# 12V_FROM_BATTERY.net
KiCad netlist of a schematic drawn in Altium Designer
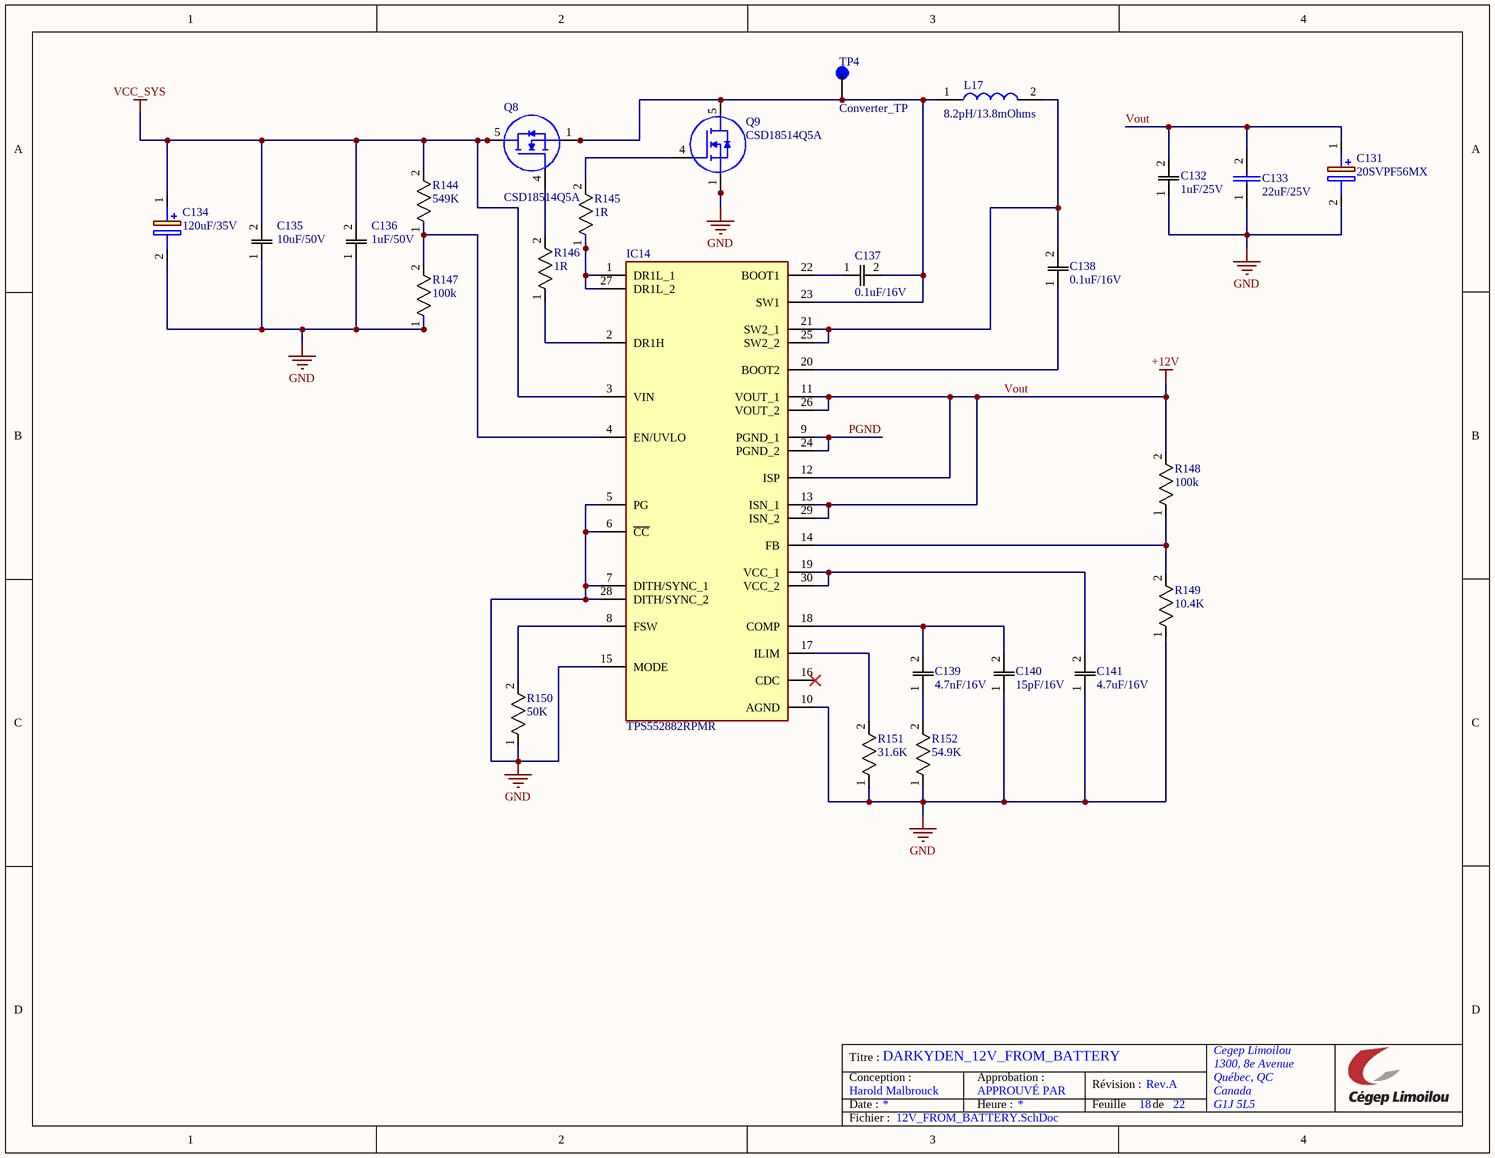
[diagram p0: 12V_FROM_BATTERY.SchDoc]

(export (version "E")
  (design (tool "Eeschema 10.0.6"))
  (components
    (comp (ref "C131")
      (value "20SVPF56MX")
      (footprint "SamacSys:16SVF82M")
      (description "56uF 20VDC 20%( Cap Aluminum Polymer SMD 0.03 Ohm 2800mA 5000h 105C T/R")
      (fields (field (name "MOUSER PART NUMBER") "667-20SVPF56MX") (field (name "MANUFACTURER") "Panasonic"))
      (libsource (lib "SamacSys") (part "20SVPF56MX"))
    )
    (comp (ref "C132")
      (value "1uF/25V")
      (footprint "SamacSys:C0805")
      (description "1 µF, 25 V (DC), ±10 %, SMD 0805, X7R, C0805C105K3RAC7800")
      (fields
        (field (name "MANUFACTURER_PART_NUMBER") "C0805C105K3RACTU")
        (field (name "MOUSER PART NUMBER") "80-C0805C105K3R")
      )
      (libsource (lib "SamacSys") (part "C0805C105K3RACTU"))
    )
    (comp (ref "C133")
      (value "22uF/25V")
      (footprint "SamacSys:CAPC3225X270N")
      (description "1210 22 uF 25 V ±10% Tolerance X5R SMT Multilayer Ceramic Capacitor")
      (fields
        (field (name "MANUFACTURER_PART_NUMBER") "GRM32ER61E226KE15L")
        (field (name "MOUSER PART NUMBER") "81-GRM32ER61E226KE15")
      )
      (libsource (lib "SamacSys") (part "GRM32ER61E226KE15L"))
    )
    (comp (ref "C134")
      (value "120uF/35V")
      (footprint "SamacSys:16SVF1000M")
      (description "120uF 35VDC 20% Cap Aluminum Polymer   SMD 0.018 Ohm 4400mA 5000h 105C T/R")
      (fields
        (field (name "MANUFACTURER_PART_NUMBER") "35SVPF120M")
        (field (name "MOUSER PART NUMBER") "667-35SVPF120M")
      )
      (libsource (lib "SamacSys") (part "35SVPF120M"))
    )
    (comp (ref "C135")
      (value "10uF/50V")
      (footprint "SamacSys:CAPC3225X230N")
      (description "10 uF 50 V 1210 ±20 % Tolerance X7R SMT Multilayer Ceramic Capacitor")
      (fields
        (field (name "MANUFACTURER_PART_NUMBER") "C3225X7R1H106M250AC")
        (field (name "MOUSER PART NUMBER") "810-C3225X7R1H106MAC")
      )
      (libsource (lib "SamacSys") (part "C3225X7R1H106M250AC"))
    )
    (comp (ref "C136")
      (value "1uF/50V")
      (footprint "SamacSys:CAPC1608X80N")
      (description "1uF / 50 V, X5R,  Surface Mount, 0603")
      (fields
        (field (name "MANUFACTURER_PART_NUMBER") "C1608X5R1H105K080AB")
        (field (name "MOUSER PART NUMBER") "810-C1608X5R1H105K")
      )
      (libsource (lib "SamacSys") (part "C1608X5R1H105K080AB"))
    )
    (comp (ref "C137")
      (value "0.1uF/16V")
      (footprint "CAPC220145_88N_KEM")
      (description "0.1uF/16V ±10% X7R 0805 (2012METRIC) Ceramic Capacitor SMD Auto X7R")
      (fields
        (field (name "MANUFACTURER") "KEMET")
        (field (name "MANUFACTURER PART NUMBER") "C0805C104K4RACAUTO")
      )
      (libsource (lib "C0805C104K4RACAUTO") (part "C0805C104K4RACAUTO"))
    )
    (comp (ref "C138")
      (value "0.1uF/16V")
      (footprint "CAPC220145_88N_KEM")
      (description "0.1uF/16V ±10% X7R 0805 (2012METRIC) Ceramic Capacitor SMD Auto X7R")
      (fields
        (field (name "MANUFACTURER") "KEMET")
        (field (name "MANUFACTURER PART NUMBER") "C0805C104K4RACAUTO")
      )
      (libsource (lib "C0805C104K4RACAUTO") (part "C0805C104K4RACAUTO"))
    )
    (comp (ref "C139")
      (value "4.7nF/16V")
      (footprint "CAPC220145_88N_KEM")
      (description "4.7nF, 16VDC, 10-% Tol, 10+% Tol, X7R-TC Code, -15, 15%-TC RoHS Compliant: Yes")
      (fields
        (field (name "MANUFACTURER") "KEMET")
        (field (name "MANUFACTURER PART NUMBER") "C0805C472K4RACTU")
      )
      (libsource (lib "C0805C472K4RACTU") (part "C0805C472K4RACTU"))
    )
    (comp (ref "C140")
      (value "15pF/16V")
      (footprint "CAPC220145_88N_KEM")
      (description "15 pF, 16 V, ± 10%, C0G (NP0), 0805 [2012 Metric]")
      (fields
        (field (name "MANUFACTURER") "KEMET")
        (field (name "MANUFACTURER PART NUMBER") "C0805C150K4GACTU")
      )
      (libsource (lib "C0805C150K4GACTU") (part "C0805C150K4GACTU"))
    )
    (comp (ref "C141")
      (value "4.7uF/16V")
      (footprint "SamacSys:C0805")
      (description "4.7 uF, 16 V, ± 10%, X7R, 0805 [2012 Metric]")
      (fields
        (field (name "MANUFACTURER_PART_NUMBER") "C0805C475K4RACTU")
        (field (name "MOUSER PART NUMBER") "80-C0805C475K4R")
      )
      (libsource (lib "SamacSys") (part "C0805C475K4RACTU"))
    )
    (comp (ref "IC14")
      (value "TPS552882RPMR")
      (footprint "SamacSys:TPS552882RPMR")
      (description "36-V, 16-A buck-boost converter 26-VQFN-HR -40 to 125")
      (fields
        (field (name "MOUSER PART NUMBER") "595-TPS552882RPMR")
        (field (name "MANUFACTURER") "Texas Instruments")
      )
      (libsource (lib "SamacSys") (part "TPS552882RPMR"))
    )
    (comp (ref "L17")
      (value "8.2pH/13.8mOhms")
      (footprint "SamacSys:INDPM135126X650N")
      (description "Inductor Power Shielded/Molded Wirewound 8.2uH 20% 100KHz 15A 0.0138Ohm DCR Automotive T/R")
      (fields
        (field (name "MANUFACTURER_PART_NUMBER") "PA4343.822ANLT")
        (field (name "MOUSER PART NUMBER") "673-PA4343.822ANLT")
      )
      (libsource (lib "SamacSys") (part "PA4343.822ANLT"))
    )
    (comp (ref "Q8")
      (value "CSD18514Q5A")
      (footprint "SamacSys:CSD18514Q5A")
      (description "MOSFET N-Channel 40 V 89A (Tc) 74W (Tc) Surface Mount 8-VSONP (5x6)")
      (fields (field (name "MOUSER PART NUMBER") "595-CSD18514Q5A"))
      (libsource (lib "SamacSys") (part "CSD18514Q5A"))
    )
    (comp (ref "Q9")
      (value "CSD18514Q5A")
      (footprint "SamacSys:CSD18514Q5A")
      (description "MOSFET N-Channel 40 V 89A (Tc) 74W (Tc) Surface Mount 8-VSONP (5x6)")
      (fields (field (name "MOUSER PART NUMBER") "595-CSD18514Q5A"))
      (libsource (lib "SamacSys") (part "CSD18514Q5A"))
    )
    (comp (ref "R144")
      (value "549K")
      (footprint "RC0603N_PAN")
      (description "549 kOhm, ± 1%, 100 mW, 0603 [1608 Metric], Thick Film, Precision")
      (fields
        (field (name "MANUFACTURER") "Panasonic")
        (field (name "MANUFACTURER PART NUMBER") "ERJ-3EKF5493V")
      )
      (libsource (lib "ERJ-3EKF5493V") (part "ERJ-3EKF5493V"))
    )
    (comp (ref "R145")
      (value "1R")
      (footprint "SamacSys:ERJ3EKF1000V")
      (description "1 Ohm 5% 1/10W  Res Thick Film 0603 -100ppm/ to 600¦")
      (fields
        (field (name "MANUFACTURER_PART_NUMBER") "ERJ-3GEYJ1R0V")
        (field (name "MOUSER PART NUMBER") "667-ERJ-3GEYJ1R0V")
      )
      (libsource (lib "SamacSys") (part "ERJ-3GEYJ1R0V"))
    )
    (comp (ref "R146")
      (value "1R")
      (footprint "SamacSys:ERJ3EKF1000V")
      (description "1 Ohm 5% 1/10W  Res Thick Film 0603 -100ppm/ to 600¦")
      (fields
        (field (name "MANUFACTURER_PART_NUMBER") "ERJ-3GEYJ1R0V")
        (field (name "MOUSER PART NUMBER") "667-ERJ-3GEYJ1R0V")
      )
      (libsource (lib "SamacSys") (part "ERJ-3GEYJ1R0V"))
    )
    (comp (ref "R147")
      (value "100k")
      (footprint "SamacSys:ERJ3EKF1000V")
      (description "100K Ohm 5%  Res Thick Film 0603 1/10W +/-200ppm/ßC Molded SMD Punched Carrier T/R")
      (fields
        (field (name "MANUFACTURER_PART_NUMBER") "ERJ-3GEYJ104V")
        (field (name "MOUSER PART NUMBER") "667-ERJ-3GEYJ104V")
      )
      (libsource (lib "SamacSys") (part "ERJ-3GEYJ104V"))
    )
    (comp (ref "R148")
      (value "100k")
      (footprint "SamacSys:ERJ3EKF1000V")
      (description "100K Ohm 5%  Res Thick Film 0603 1/10W +/-200ppm/ßC Molded SMD Punched Carrier T/R")
      (fields
        (field (name "MANUFACTURER_PART_NUMBER") "ERJ-3GEYJ104V")
        (field (name "MOUSER PART NUMBER") "667-ERJ-3GEYJ104V")
      )
      (libsource (lib "SamacSys") (part "ERJ-3GEYJ104V"))
    )
    (comp (ref "R149")
      (value "10.4K")
      (footprint "RC0603N_PAN")
      (description "10.4kOhm 0.1% High Precision-High Stability Chip Resistor Thin Film 0603  Paper T/R")
      (fields (field (name "MP") "RT0603BRD0710K4L") (field (name "MANUFACTURER") "Yageo"))
      (libsource (lib "RT0603BRD0710K4L") (part "RT0603BRD0710K4L"))
    )
    (comp (ref "R150")
      (value "50K")
      (footprint "SamacSys:RESC1005X40N")
      (description "50 kΩ  Tolerance: 1.0%  Power: 63 mW  Package:0402")
      (fields
        (field (name "MANUFACTURER_PART_NUMBER") "CRCW040250K0FKED")
        (field (name "MOUSER PART NUMBER") "71-CRCW0402-50K-E3")
      )
      (libsource (lib "SamacSys") (part "CRCW040250K0FKED"))
    )
    (comp (ref "R151")
      (value "31.6K")
      (footprint "SamacSys:RESC1005X40N")
      (description "31.6 kΩ  Tolerance: 1.0%  Power: 63 mW")
      (fields
        (field (name "MANUFACTURER_PART_NUMBER") "CRCW040231K6FKED")
        (field (name "MOUSER PART NUMBER") "71-CRCW0402-31.6K-E3")
      )
      (libsource (lib "SamacSys") (part "CRCW040231K6FKED"))
    )
    (comp (ref "R152")
      (value "54.9K")
      (footprint "SamacSys:RESC1005X40N")
      (description "54.9 kΩ  Tolerance: 1.0%  Power: 63 mW  PAckage:0402")
      (fields
        (field (name "MANUFACTURER_PART_NUMBER") "CRCW040254K9FKED")
        (field (name "MOUSER PART NUMBER") "71-CRCW0402-54.9K-E3")
      )
      (libsource (lib "SamacSys") (part "CRCW040254K9FKED"))
    )
    (comp (ref "TP4")
      (value "Converter_TP")
      (footprint "KEYSTONE_5006")
      (description "Test Point Compact THM PC .350 L .125 OD Heat Resistant Nylon 46 Black ¦ Keystone Electronics 5006")
      (fields (field (name "MF") "Keystone Electronics Corp.") (field (name "MP") "5006"))
      (libsource (lib "test_point") (part "5006"))
    )
  )
  (nets
    (net (code "1") (name "+12V") (class "Default")
      (node (ref "C131") (pin "1") (pinfunction "+_1") (pintype "passive"))
      (node (ref "C132") (pin "2") (pinfunction "2_2") (pintype "passive"))
      (node (ref "C133") (pin "2") (pinfunction "2_2") (pintype "passive"))
      (node (ref "IC14") (pin "11") (pinfunction "VOUT_1_11") (pintype "passive"))
      (node (ref "IC14") (pin "12") (pinfunction "ISP_12") (pintype "passive"))
      (node (ref "IC14") (pin "13") (pinfunction "ISN_1_13") (pintype "passive"))
      (node (ref "IC14") (pin "26") (pinfunction "VOUT_2_26") (pintype "passive"))
      (node (ref "IC14") (pin "29") (pinfunction "ISN_2_29") (pintype "passive"))
      (node (ref "R148") (pin "2") (pinfunction "2_2") (pintype "passive"))
    )
    (net (code "2") (name "/PGND") (class "Default")
      (node (ref "IC14") (pin "24") (pinfunction "PGND_2_24") (pintype "passive"))
      (node (ref "IC14") (pin "9") (pinfunction "PGND_1_9") (pintype "passive"))
    )
    (net (code "3") (name "GND") (class "Default")
      (node (ref "C131") (pin "2") (pinfunction "-_2") (pintype "passive"))
      (node (ref "C132") (pin "1") (pinfunction "1_1") (pintype "passive"))
      (node (ref "C133") (pin "1") (pinfunction "1_1") (pintype "passive"))
      (node (ref "C134") (pin "2") (pinfunction "-_2") (pintype "passive"))
      (node (ref "C135") (pin "1") (pinfunction "1_1") (pintype "passive"))
      (node (ref "C136") (pin "1") (pinfunction "1_1") (pintype "passive"))
      (node (ref "C140") (pin "1") (pinfunction "1_1") (pintype "passive"))
      (node (ref "C141") (pin "1") (pinfunction "1_1") (pintype "passive"))
      (node (ref "IC14") (pin "10") (pinfunction "AGND_10") (pintype "passive"))
      (node (ref "IC14") (pin "15") (pinfunction "MODE_15") (pintype "passive"))
      (node (ref "IC14") (pin "28") (pinfunction "DITH/SYNC_2_28") (pintype "passive"))
      (node (ref "IC14") (pin "5") (pinfunction "PG_5") (pintype "passive"))
      (node (ref "IC14") (pin "6") (pinfunction "~{CC}_6") (pintype "passive"))
      (node (ref "IC14") (pin "7") (pinfunction "DITH/SYNC_1_7") (pintype "passive"))
      (node (ref "R147") (pin "1") (pinfunction "1_1") (pintype "passive"))
      (node (ref "R149") (pin "1") (pinfunction "1_1") (pintype "passive"))
      (node (ref "R150") (pin "1") (pinfunction "1_1") (pintype "passive"))
      (node (ref "R151") (pin "1") (pinfunction "1_1") (pintype "passive"))
      (node (ref "R152") (pin "1") (pinfunction "1_1") (pintype "passive"))
    )
    (net (code "4") (name "Net-(C139-Pad1)") (class "Default")
      (node (ref "C139") (pin "1") (pinfunction "1_1") (pintype "passive"))
      (node (ref "R152") (pin "2") (pinfunction "2_2") (pintype "passive"))
    )
    (net (code "5") (name "Net-(IC14-BOOT1)") (class "Default")
      (node (ref "C137") (pin "1") (pinfunction "1_1") (pintype "passive"))
      (node (ref "IC14") (pin "22") (pinfunction "BOOT1_22") (pintype "passive"))
    )
    (net (code "6") (name "Net-(IC14-BOOT2)") (class "Default")
      (node (ref "C138") (pin "1") (pinfunction "1_1") (pintype "passive"))
      (node (ref "IC14") (pin "20") (pinfunction "BOOT2_20") (pintype "passive"))
    )
    (net (code "7") (name "Net-(IC14-COMP)") (class "Default")
      (node (ref "C139") (pin "2") (pinfunction "2_2") (pintype "passive"))
      (node (ref "C140") (pin "2") (pinfunction "2_2") (pintype "passive"))
      (node (ref "IC14") (pin "18") (pinfunction "COMP_18") (pintype "passive"))
    )
    (net (code "8") (name "Net-(IC14-DR1H)") (class "Default")
      (node (ref "IC14") (pin "2") (pinfunction "DR1H_2") (pintype "passive"))
      (node (ref "R146") (pin "1") (pinfunction "1_1") (pintype "passive"))
    )
    (net (code "9") (name "Net-(IC14-DR1L_1)") (class "Default")
      (node (ref "IC14") (pin "1") (pinfunction "DR1L_1_1") (pintype "passive"))
      (node (ref "IC14") (pin "27") (pinfunction "DR1L_2_27") (pintype "passive"))
      (node (ref "R145") (pin "1") (pinfunction "1_1") (pintype "passive"))
    )
    (net (code "10") (name "Net-(IC14-EN{slash}UVLO)") (class "Default")
      (node (ref "IC14") (pin "4") (pinfunction "EN/UVLO_4") (pintype "passive"))
      (node (ref "R144") (pin "1") (pinfunction "1_1") (pintype "passive"))
      (node (ref "R147") (pin "2") (pinfunction "2_2") (pintype "passive"))
    )
    (net (code "11") (name "Net-(IC14-FB)") (class "Default")
      (node (ref "IC14") (pin "14") (pinfunction "FB_14") (pintype "passive"))
      (node (ref "R148") (pin "1") (pinfunction "1_1") (pintype "passive"))
      (node (ref "R149") (pin "2") (pinfunction "2_2") (pintype "passive"))
    )
    (net (code "12") (name "Net-(IC14-FSW)") (class "Default")
      (node (ref "IC14") (pin "8") (pinfunction "FSW_8") (pintype "passive"))
      (node (ref "R150") (pin "2") (pinfunction "2_2") (pintype "passive"))
    )
    (net (code "13") (name "Net-(IC14-ILIM)") (class "Default")
      (node (ref "IC14") (pin "17") (pinfunction "ILIM_17") (pintype "passive"))
      (node (ref "R151") (pin "2") (pinfunction "2_2") (pintype "passive"))
    )
    (net (code "14") (name "Net-(IC14-SW1)") (class "Default")
      (node (ref "C137") (pin "2") (pinfunction "2_2") (pintype "passive"))
      (node (ref "IC14") (pin "23") (pinfunction "SW1_23") (pintype "passive"))
      (node (ref "L17") (pin "1") (pinfunction "1_1") (pintype "passive"))
      (node (ref "Q8") (pin "1") (pinfunction "S_1") (pintype "passive"))
      (node (ref "Q8") (pin "2") (pinfunction "S_2_2") (pintype "passive"))
      (node (ref "Q8") (pin "3") (pinfunction "S_3_3") (pintype "passive"))
      (node (ref "Q9") (pin "5") (pinfunction "D_5") (pintype "passive"))
      (node (ref "Q9") (pin "6") (pinfunction "D_2_6") (pintype "passive"))
      (node (ref "Q9") (pin "7") (pinfunction "D_3_7") (pintype "passive"))
      (node (ref "Q9") (pin "8") (pinfunction "D_4_8") (pintype "passive"))
      (node (ref "Q9") (pin "9") (pinfunction "D_5_9") (pintype "passive"))
      (node (ref "TP4") (pin "TP") (pinfunction "TP_TP") (pintype "passive"))
    )
    (net (code "15") (name "Net-(IC14-SW2_1)") (class "Default")
      (node (ref "C138") (pin "2") (pinfunction "2_2") (pintype "passive"))
      (node (ref "IC14") (pin "21") (pinfunction "SW2_1_21") (pintype "passive"))
      (node (ref "IC14") (pin "25") (pinfunction "SW2_2_25") (pintype "passive"))
      (node (ref "L17") (pin "2") (pinfunction "2_2") (pintype "passive"))
    )
    (net (code "16") (name "Net-(IC14-VCC_1)") (class "Default")
      (node (ref "C141") (pin "2") (pinfunction "2_2") (pintype "passive"))
      (node (ref "IC14") (pin "19") (pinfunction "VCC_1_19") (pintype "passive"))
      (node (ref "IC14") (pin "30") (pinfunction "VCC_2_30") (pintype "passive"))
    )
    (net (code "17") (name "Net-(Q8-G)") (class "Default")
      (node (ref "Q8") (pin "4") (pinfunction "G_4") (pintype "passive"))
      (node (ref "R146") (pin "2") (pinfunction "2_2") (pintype "passive"))
    )
    (net (code "18") (name "Net-(Q9-G)") (class "Default")
      (node (ref "Q9") (pin "4") (pinfunction "G_4") (pintype "passive"))
      (node (ref "R145") (pin "2") (pinfunction "2_2") (pintype "passive"))
    )
    (net (code "19") (name "Net-(Q9-S)") (class "Default")
      (node (ref "Q9") (pin "1") (pinfunction "S_1") (pintype "passive"))
      (node (ref "Q9") (pin "2") (pinfunction "S_2_2") (pintype "passive"))
      (node (ref "Q9") (pin "3") (pinfunction "S_3_3") (pintype "passive"))
    )
    (net (code "20") (name "VCC_SYS") (class "Default")
      (node (ref "C134") (pin "1") (pinfunction "+_1") (pintype "passive"))
      (node (ref "C135") (pin "2") (pinfunction "2_2") (pintype "passive"))
      (node (ref "C136") (pin "2") (pinfunction "2_2") (pintype "passive"))
      (node (ref "IC14") (pin "3") (pinfunction "VIN_3") (pintype "passive"))
      (node (ref "Q8") (pin "5") (pinfunction "D_5") (pintype "passive"))
      (node (ref "Q8") (pin "6") (pinfunction "D_2_6") (pintype "passive"))
      (node (ref "Q8") (pin "7") (pinfunction "D_3_7") (pintype "passive"))
      (node (ref "Q8") (pin "8") (pinfunction "D_4_8") (pintype "passive"))
      (node (ref "Q8") (pin "9") (pinfunction "D_5_9") (pintype "passive"))
      (node (ref "R144") (pin "2") (pinfunction "2_2") (pintype "passive"))
    )
    (net (code "21") (name "unconnected-(IC14-CDC-Pad16)") (class "Default")
      (node (ref "IC14") (pin "16") (pinfunction "CDC_16") (pintype "passive+no_connect"))
    )
  )
)
